# sensor.net
KiCad netlist of a schematic drawn in Altium Designer
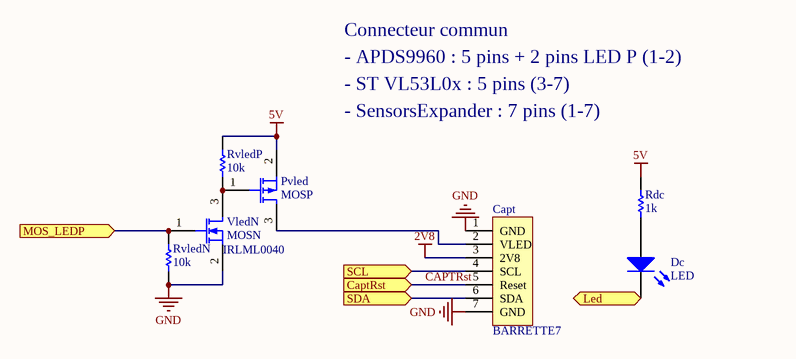
[diagram p0: sensor.SchDoc]

(export (version "E")
  (design (tool "Eeschema 10.0.6"))
  (components
    (comp (ref "Capt")
      (value "BARRETTE7")
      (footprint "MOLEX7_2.50MM")
      (description "Header, 6-Pin")
      (fields (field (name "PUBLISHER") "Altium Limited"))
      (libsource (lib "Connecteur") (part "BARRETTE7"))
    )
    (comp (ref "Dc")
      (value "LED")
      (footprint "LED_0805")
      (description "Typical LED")
      (fields (field (name "PUBLISHER") "Altium Limited"))
      (libsource (lib "_ROBOT") (part "LED"))
    )
    (comp (ref "Pvled")
      (value "MOSP")
      (footprint "SOT23-3N")
      (description "P-Channel MOSFET")
      (fields (field (name "PUBLISHER") "Altium Limited"))
      (libsource (lib "_ROBOT") (part "Transistor MOSFET-P"))
    )
    (comp (ref "Rdc")
      (value "1k")
      (footprint "R1206_N")
      (description "Resistor")
      (fields (field (name "PUBLISHER") "Altium Limited"))
      (libsource (lib "_ROBOT") (part "Resistor"))
    )
    (comp (ref "RvledN")
      (value "10k")
      (footprint "R1206_N")
      (description "Resistor")
      (fields (field (name "PUBLISHER") "Altium Limited"))
      (libsource (lib "_ROBOT") (part "Resistor"))
    )
    (comp (ref "RvledP")
      (value "10k")
      (footprint "R1206_N")
      (description "Resistor")
      (fields (field (name "PUBLISHER") "Altium Limited"))
      (libsource (lib "_ROBOT") (part "Resistor"))
    )
    (comp (ref "VledN")
      (value "MOSN")
      (footprint "SOT23-3N")
      (description "N-Channel MOSFET")
      (fields (field (name "ALTIUM_UNNAMED_1") "IRLML0040") (field (name "PUBLISHER") "Altium Limited"))
      (libsource (lib "_ROBOT") (part "Transistor MOSFET-N"))
    )
  )
  (nets
    (net (code "1") (name "/CAPTRst") (class "Default")
      (node (ref "Capt") (pin "5") (pinfunction "Reset_5") (pintype "passive"))
    )
    (net (code "2") (name "/Led") (class "Default")
      (node (ref "Dc") (pin "2") (pinfunction "K_2") (pintype "passive"))
    )
    (net (code "3") (name "/MOS_LEDP") (class "Default")
      (node (ref "RvledN") (pin "1") (pinfunction "1_1") (pintype "passive"))
      (node (ref "VledN") (pin "1") (pinfunction "G_1") (pintype "passive"))
    )
    (net (code "4") (name "/SCL") (class "Default")
      (node (ref "Capt") (pin "4") (pinfunction "SCL_4") (pintype "passive"))
    )
    (net (code "5") (name "/SDA") (class "Default")
      (node (ref "Capt") (pin "6") (pinfunction "SDA_6") (pintype "passive"))
    )
    (net (code "6") (name "2V8") (class "Default")
      (node (ref "Capt") (pin "3") (pinfunction "2V8_3") (pintype "passive"))
    )
    (net (code "7") (name "5V") (class "Default")
      (node (ref "Pvled") (pin "2") (pinfunction "S_2") (pintype "passive"))
      (node (ref "Rdc") (pin "1") (pinfunction "1_1") (pintype "passive"))
      (node (ref "RvledP") (pin "1") (pinfunction "1_1") (pintype "passive"))
    )
    (net (code "8") (name "GND") (class "Default")
      (node (ref "Capt") (pin "1") (pinfunction "GND_1") (pintype "passive"))
      (node (ref "Capt") (pin "7") (pinfunction "GND_7") (pintype "passive"))
      (node (ref "RvledN") (pin "2") (pinfunction "2_2") (pintype "passive"))
      (node (ref "VledN") (pin "2") (pinfunction "S_2") (pintype "passive"))
    )
    (net (code "9") (name "Net-(Capt-VLED)") (class "Default")
      (node (ref "Capt") (pin "2") (pinfunction "VLED_2") (pintype "passive"))
      (node (ref "Pvled") (pin "3") (pinfunction "D_3") (pintype "passive"))
    )
    (net (code "10") (name "Net-(Dc-A)") (class "Default")
      (node (ref "Dc") (pin "1") (pinfunction "A_1") (pintype "passive"))
      (node (ref "Rdc") (pin "2") (pinfunction "2_2") (pintype "passive"))
    )
    (net (code "11") (name "Net-(Pvled-G)") (class "Default")
      (node (ref "Pvled") (pin "1") (pinfunction "G_1") (pintype "passive"))
      (node (ref "RvledP") (pin "2") (pinfunction "2_2") (pintype "passive"))
      (node (ref "VledN") (pin "3") (pinfunction "D_3") (pintype "passive"))
    )
  )
)
